# ISEPIC_Cartridge_for_C64.net
KiCad netlist of a schematic drawn in Altium Designer
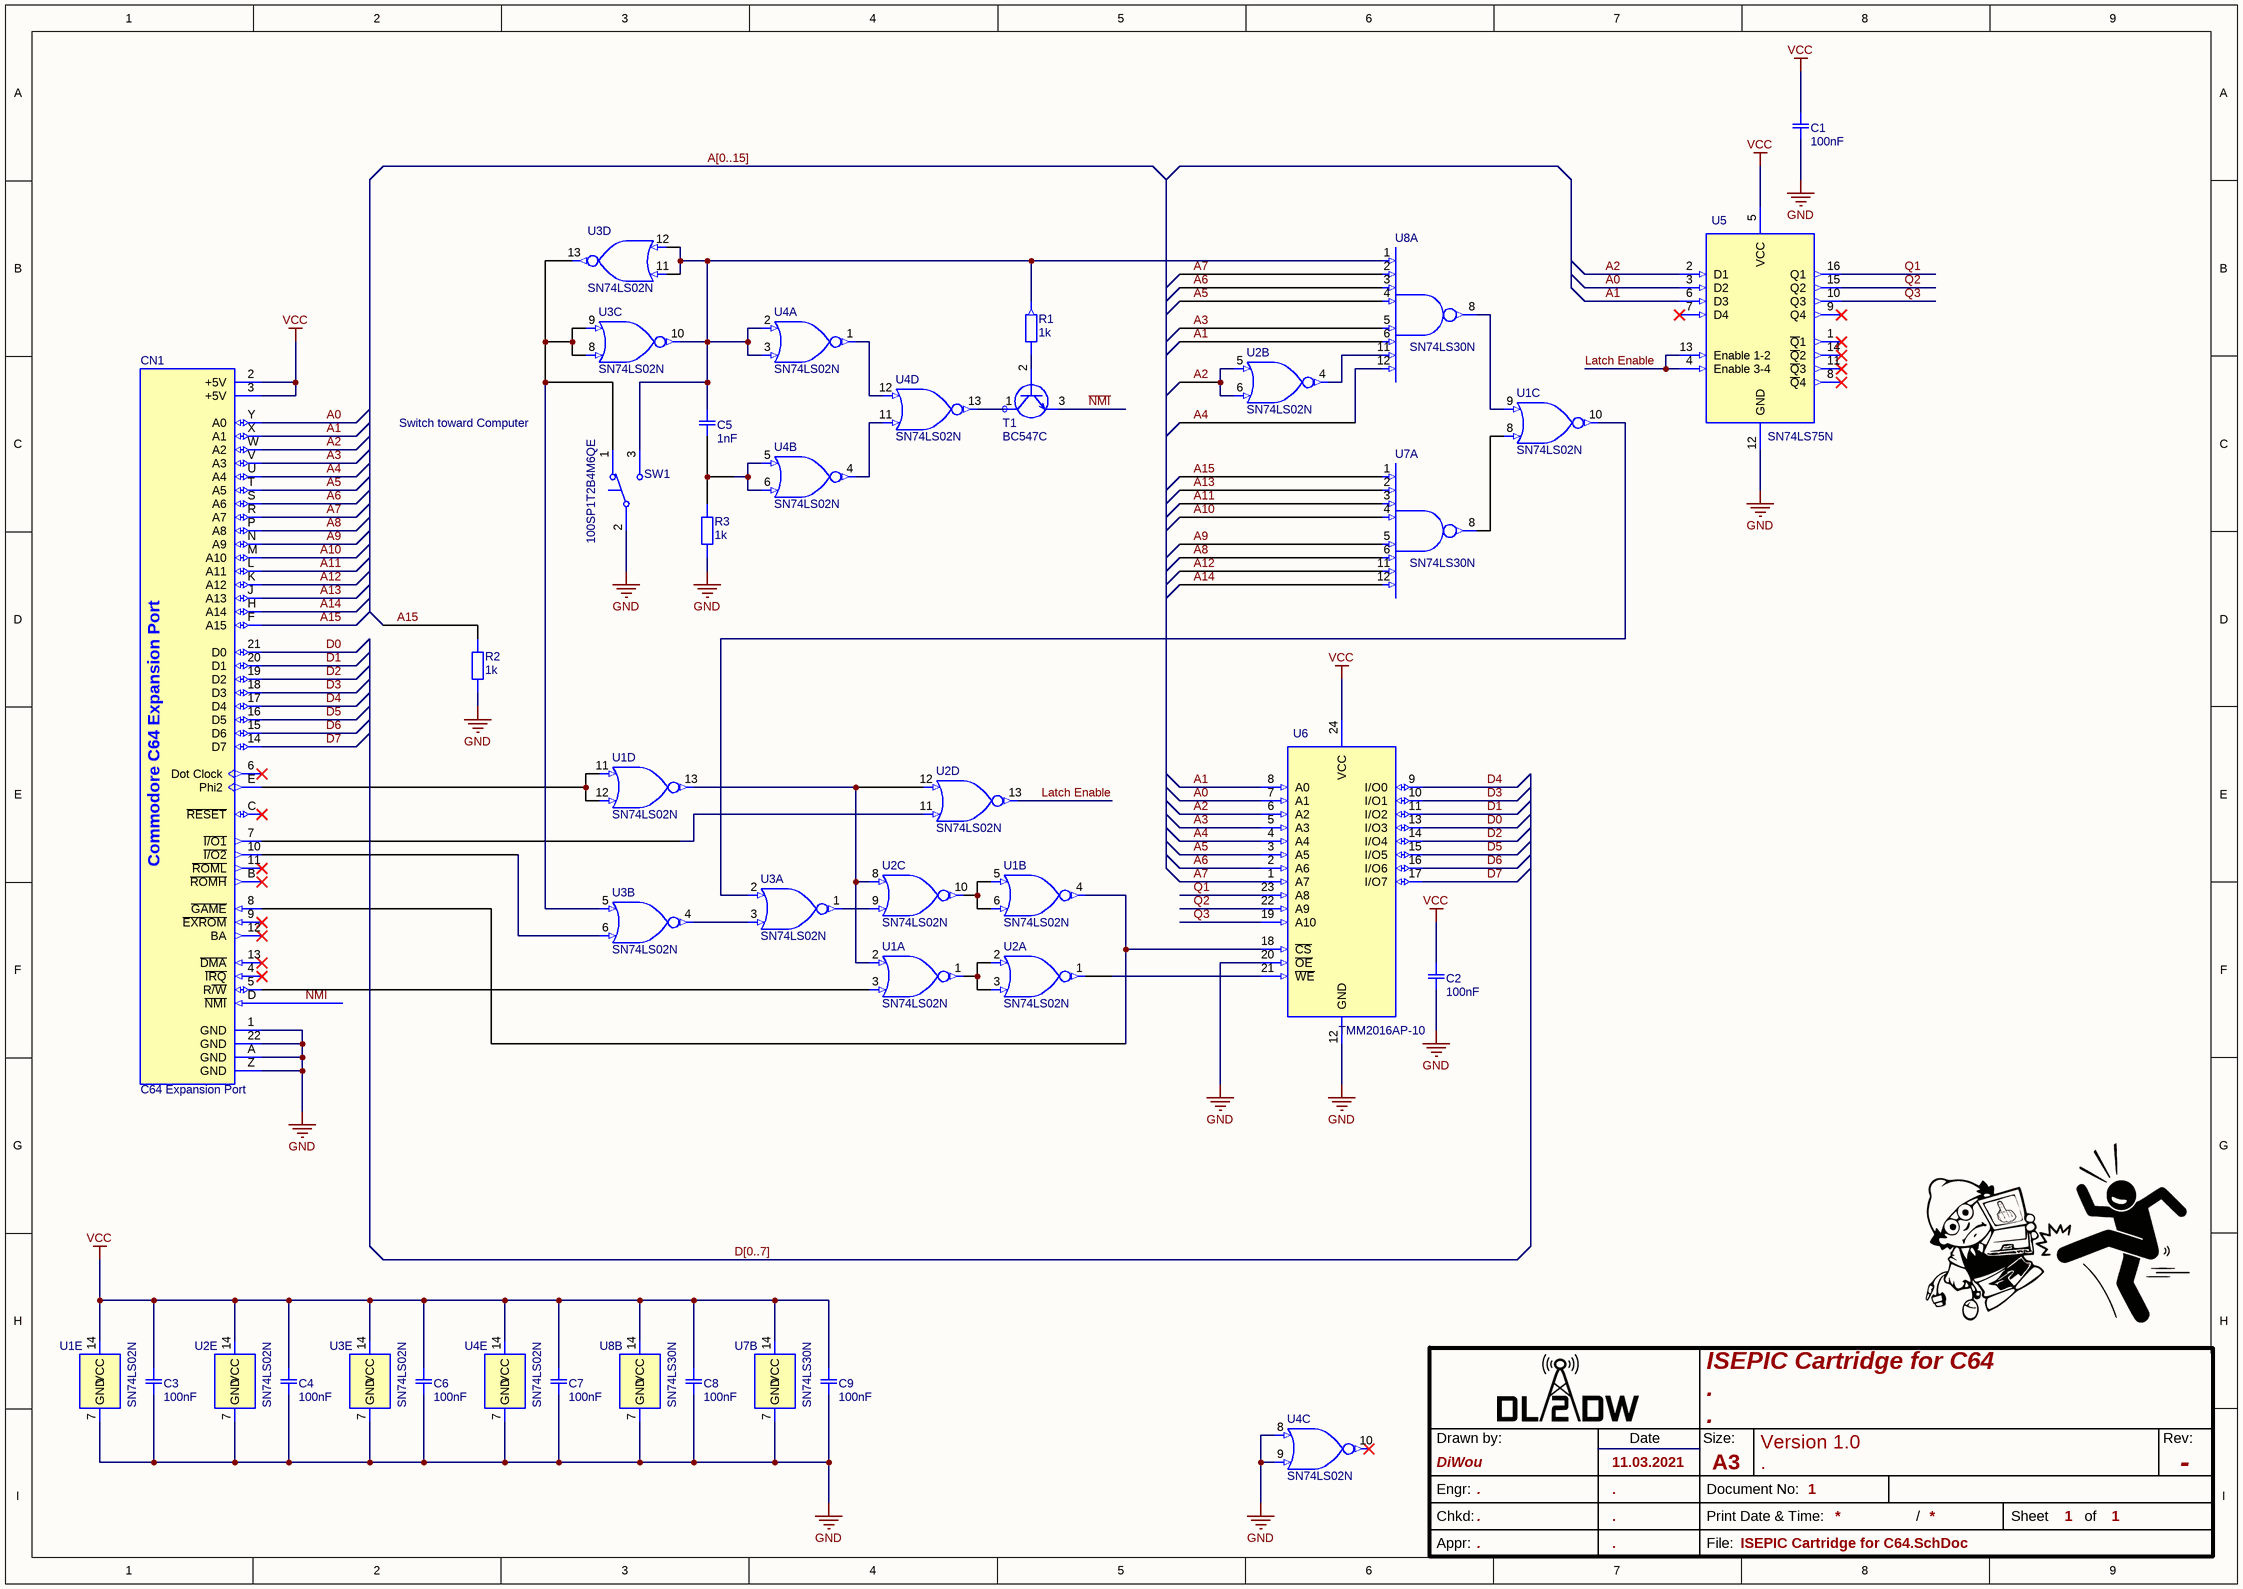
[diagram p0: ISEPIC Cartridge for C64.SchDoc]

(export (version "E")
  (design (tool "Eeschema 10.0.6"))
  (components
    (comp (ref "C1")
      (value "100nF")
      (footprint "CAP Disc 100nF P2.54mm D5.5mm T3mm")
      (description "Ceramic Disc Capacitors 100nF -20%~+80% 50V Through Hole,P=2.54mm RoHS")
      (libsource (lib "PCB-Tech Cloud") (part "Capacitor"))
    )
    (comp (ref "C2")
      (value "100nF")
      (footprint "CAP Disc 100nF P2.54mm D5.5mm T3mm")
      (description "Ceramic Disc Capacitors 100nF -20%~+80% 50V Through Hole,P=2.54mm RoHS")
      (libsource (lib "PCB-Tech Cloud") (part "Capacitor"))
    )
    (comp (ref "C3")
      (value "100nF")
      (footprint "CAP Disc 100nF P2.54mm D5.5mm T3mm")
      (description "Ceramic Disc Capacitors 100nF -20%~+80% 50V Through Hole,P=2.54mm RoHS")
      (libsource (lib "PCB-Tech Cloud") (part "Capacitor"))
    )
    (comp (ref "C4")
      (value "100nF")
      (footprint "CAP Disc 100nF P2.54mm D5.5mm T3mm")
      (description "Ceramic Disc Capacitors 100nF -20%~+80% 50V Through Hole,P=2.54mm RoHS")
      (libsource (lib "PCB-Tech Cloud") (part "Capacitor"))
    )
    (comp (ref "C5")
      (value "1nF")
      (footprint "K102J15C0GF5TL2")
      (description "CAP CER 1000PF 50V C0G/NP0 RAD")
      (fields (field (name "TOLERANCE") "5%") (field (name "VOLTAGE") "50V"))
      (libsource (lib "PCB-Tech Cloud") (part "Capacitor"))
    )
    (comp (ref "C6")
      (value "100nF")
      (footprint "CAP Disc 100nF P2.54mm D5.5mm T3mm")
      (description "Ceramic Disc Capacitors 100nF -20%~+80% 50V Through Hole,P=2.54mm RoHS")
      (libsource (lib "PCB-Tech Cloud") (part "Capacitor"))
    )
    (comp (ref "C7")
      (value "100nF")
      (footprint "CAP Disc 100nF P2.54mm D5.5mm T3mm")
      (description "Ceramic Disc Capacitors 100nF -20%~+80% 50V Through Hole,P=2.54mm RoHS")
      (libsource (lib "PCB-Tech Cloud") (part "Capacitor"))
    )
    (comp (ref "C8")
      (value "100nF")
      (footprint "CAP Disc 100nF P2.54mm D5.5mm T3mm")
      (description "Ceramic Disc Capacitors 100nF -20%~+80% 50V Through Hole,P=2.54mm RoHS")
      (libsource (lib "PCB-Tech Cloud") (part "Capacitor"))
    )
    (comp (ref "C9")
      (value "100nF")
      (footprint "CAP Disc 100nF P2.54mm D5.5mm T3mm")
      (description "Ceramic Disc Capacitors 100nF -20%~+80% 50V Through Hole,P=2.54mm RoHS")
      (libsource (lib "PCB-Tech Cloud") (part "Capacitor"))
    )
    (comp (ref "CN1")
      (value "C64 Expansion Port")
      (footprint "C64 Expansion Port EDGE Connector")
      (description "Expansion Port EDGE Connector for Interface Cards")
      (libsource (lib "PCB-Tech Cloud") (part "C64 Expansion Port"))
    )
    (comp (ref "R1")
      (value "1k")
      (footprint "1,0 kOhm R Axial DIN0207 L6.3mm D2.5mm P7.62mm Horizontal")
      (description "RES 1K OHM 1/4W 5% AXIAL")
      (fields (field (name "TOLERANCE") "5%"))
      (libsource (lib "PCB-Tech Cloud") (part "Resistor"))
    )
    (comp (ref "R2")
      (value "1k")
      (footprint "1,0 kOhm R Axial DIN0207 L6.3mm D2.5mm P7.62mm Horizontal")
      (description "RES 1K OHM 1/4W 5% AXIAL")
      (fields (field (name "TOLERANCE") "5%"))
      (libsource (lib "PCB-Tech Cloud") (part "Resistor"))
    )
    (comp (ref "R3")
      (value "1k")
      (footprint "1,0 kOhm R Axial DIN0207 L6.3mm D2.5mm P7.62mm Horizontal")
      (description "RES 1K OHM 1/4W 5% AXIAL")
      (fields (field (name "TOLERANCE") "5%"))
      (libsource (lib "PCB-Tech Cloud") (part "Resistor"))
    )
    (comp (ref "SW1")
      (value "100SP1T2B4M6QE")
      (footprint "Toogle Switch SPDT 100SP1T2B4M6QE")
      (description "SWITCH TOGGLE SPDT 5A 120V")
      (libsource (lib "PCB-Tech Cloud") (part "Switch Push SPDT"))
    )
    (comp (ref "T1")
      (value "BC547C")
      (footprint "BC547C")
      (description "BC547C Diotec Bipolar NPN Transistor 45V")
      (libsource (lib "PCB-Tech Cloud") (part "Transistor NPN CBE"))
    )
    (comp (ref "U1")
      (value "SN74LS02N")
      (footprint "SN74LS02N with Socket")
      (description "IC GATE NOR 4CH 2-INP 14DIP")
      (libsource (lib "PCB-Tech Cloud") (part "74xx02"))
    )
    (comp (ref "U2")
      (value "SN74LS02N")
      (footprint "SN74LS02N with Socket")
      (description "IC GATE NOR 4CH 2-INP 14DIP")
      (libsource (lib "") (part "74xx02_1"))
    )
    (comp (ref "U3")
      (value "SN74LS02N")
      (footprint "SN74LS02N with Socket")
      (description "IC GATE NOR 4CH 2-INP 14DIP")
      (libsource (lib "PCB-Tech Cloud") (part "74xx02"))
    )
    (comp (ref "U4")
      (value "SN74LS02N")
      (footprint "SN74LS02N with Socket")
      (description "IC GATE NOR 4CH 2-INP 14DIP")
      (libsource (lib "PCB-Tech Cloud") (part "74xx02"))
    )
    (comp (ref "U5")
      (value "SN74LS75N")
      (footprint "SN74LS75N with Socket")
      (description "Latch Transparent 4-CH D-Type 16-Pin PDIP Tube")
      (libsource (lib "PCB-Tech Cloud") (part "74xx75"))
    )
    (comp (ref "U6")
      (value "TMM2016AP-10")
      (footprint "Toshiba TMM2016AP-10 - with Socket")
      (description "Integrated Circuit Memory 2016/TMM2016AP10 TOSHIBA Static RAM memory prog. volatille KX8=2")
      (libsource (lib "PCB-Tech Cloud") (part "2048 WORD x 8 BIT STATIC RAM"))
    )
    (comp (ref "U7")
      (value "SN74LS30N")
      (footprint "SN74LS30N with Socket")
      (description "IC GATE NAND 1CH 8-INP 14DIP")
      (libsource (lib "PCB-Tech Cloud") (part "74xx30"))
    )
    (comp (ref "U8")
      (value "SN74LS30N")
      (footprint "SN74LS30N with Socket")
      (description "IC GATE NAND 1CH 8-INP 14DIP")
      (libsource (lib "PCB-Tech Cloud") (part "74xx30"))
    )
  )
  (nets
    (net (code "1") (name "/A0") (class "Default")
      (node (ref "CN1") (pin "Y") (pinfunction "A0_Y") (pintype "bidirectional"))
      (node (ref "U5") (pin "3") (pinfunction "D2_3") (pintype "input"))
      (node (ref "U6") (pin "7") (pinfunction "A1_7") (pintype "input"))
    )
    (net (code "2") (name "/A1") (class "Default")
      (node (ref "CN1") (pin "X") (pinfunction "A1_X") (pintype "bidirectional"))
      (node (ref "U5") (pin "6") (pinfunction "D3_6") (pintype "input"))
      (node (ref "U6") (pin "8") (pinfunction "A0_8") (pintype "input"))
      (node (ref "U8") (pin "6") (pinfunction "F_6") (pintype "input"))
    )
    (net (code "3") (name "/A2") (class "Default")
      (node (ref "CN1") (pin "W") (pinfunction "A2_W") (pintype "bidirectional"))
      (node (ref "U2") (pin "5") (pinfunction "2A_5") (pintype "input"))
      (node (ref "U2") (pin "6") (pinfunction "2B_6") (pintype "input"))
      (node (ref "U5") (pin "2") (pinfunction "D1_2") (pintype "input"))
      (node (ref "U6") (pin "6") (pinfunction "A2_6") (pintype "input"))
    )
    (net (code "4") (name "/A3") (class "Default")
      (node (ref "CN1") (pin "V") (pinfunction "A3_V") (pintype "bidirectional"))
      (node (ref "U6") (pin "5") (pinfunction "A3_5") (pintype "input"))
      (node (ref "U8") (pin "5") (pinfunction "E_5") (pintype "input"))
    )
    (net (code "5") (name "/A4") (class "Default")
      (node (ref "CN1") (pin "U") (pinfunction "A4_U") (pintype "bidirectional"))
      (node (ref "U6") (pin "4") (pinfunction "A4_4") (pintype "input"))
      (node (ref "U8") (pin "12") (pinfunction "H_12") (pintype "input"))
    )
    (net (code "6") (name "/A5") (class "Default")
      (node (ref "CN1") (pin "T") (pinfunction "A5_T") (pintype "bidirectional"))
      (node (ref "U6") (pin "3") (pinfunction "A5_3") (pintype "input"))
      (node (ref "U8") (pin "4") (pinfunction "D_4") (pintype "input"))
    )
    (net (code "7") (name "/A6") (class "Default")
      (node (ref "CN1") (pin "S") (pinfunction "A6_S") (pintype "bidirectional"))
      (node (ref "U6") (pin "2") (pinfunction "A6_2") (pintype "input"))
      (node (ref "U8") (pin "3") (pinfunction "C_3") (pintype "input"))
    )
    (net (code "8") (name "/A7") (class "Default")
      (node (ref "CN1") (pin "R") (pinfunction "A7_R") (pintype "bidirectional"))
      (node (ref "U6") (pin "1") (pinfunction "A7_1") (pintype "input"))
      (node (ref "U8") (pin "2") (pinfunction "B_2") (pintype "input"))
    )
    (net (code "9") (name "/A8") (class "Default")
      (node (ref "CN1") (pin "P") (pinfunction "A8_P") (pintype "bidirectional"))
      (node (ref "U7") (pin "6") (pinfunction "F_6") (pintype "input"))
    )
    (net (code "10") (name "/A9") (class "Default")
      (node (ref "CN1") (pin "N") (pinfunction "A9_N") (pintype "bidirectional"))
      (node (ref "U7") (pin "5") (pinfunction "E_5") (pintype "input"))
    )
    (net (code "11") (name "/A10") (class "Default")
      (node (ref "CN1") (pin "M") (pinfunction "A10_M") (pintype "bidirectional"))
      (node (ref "U7") (pin "4") (pinfunction "D_4") (pintype "input"))
    )
    (net (code "12") (name "/A11") (class "Default")
      (node (ref "CN1") (pin "L") (pinfunction "A11_L") (pintype "bidirectional"))
      (node (ref "U7") (pin "3") (pinfunction "C_3") (pintype "input"))
    )
    (net (code "13") (name "/A12") (class "Default")
      (node (ref "CN1") (pin "K") (pinfunction "A12_K") (pintype "bidirectional"))
      (node (ref "U7") (pin "11") (pinfunction "F_11") (pintype "input"))
    )
    (net (code "14") (name "/A13") (class "Default")
      (node (ref "CN1") (pin "J") (pinfunction "A13_J") (pintype "bidirectional"))
      (node (ref "U7") (pin "2") (pinfunction "B_2") (pintype "input"))
    )
    (net (code "15") (name "/A14") (class "Default")
      (node (ref "CN1") (pin "H") (pinfunction "A14_H") (pintype "bidirectional"))
      (node (ref "U7") (pin "12") (pinfunction "H_12") (pintype "input"))
    )
    (net (code "16") (name "/A15") (class "Default")
      (node (ref "CN1") (pin "F") (pinfunction "A15_F") (pintype "bidirectional"))
      (node (ref "R2") (pin "1") (pinfunction "1_1") (pintype "passive"))
      (node (ref "U7") (pin "1") (pinfunction "A_1") (pintype "input"))
    )
    (net (code "18") (name "/D0") (class "Default")
      (node (ref "CN1") (pin "21") (pinfunction "D0_21") (pintype "bidirectional"))
      (node (ref "U6") (pin "13") (pinfunction "I/O3_13") (pintype "bidirectional"))
    )
    (net (code "19") (name "/D1") (class "Default")
      (node (ref "CN1") (pin "20") (pinfunction "D1_20") (pintype "bidirectional"))
      (node (ref "U6") (pin "11") (pinfunction "I/O2_11") (pintype "bidirectional"))
    )
    (net (code "20") (name "/D2") (class "Default")
      (node (ref "CN1") (pin "19") (pinfunction "D2_19") (pintype "bidirectional"))
      (node (ref "U6") (pin "14") (pinfunction "I/O4_14") (pintype "bidirectional"))
    )
    (net (code "21") (name "/D3") (class "Default")
      (node (ref "CN1") (pin "18") (pinfunction "D3_18") (pintype "bidirectional"))
      (node (ref "U6") (pin "10") (pinfunction "I/O1_10") (pintype "bidirectional"))
    )
    (net (code "22") (name "/D4") (class "Default")
      (node (ref "CN1") (pin "17") (pinfunction "D4_17") (pintype "bidirectional"))
      (node (ref "U6") (pin "9") (pinfunction "I/O0_9") (pintype "bidirectional"))
    )
    (net (code "23") (name "/D5") (class "Default")
      (node (ref "CN1") (pin "16") (pinfunction "D5_16") (pintype "bidirectional"))
      (node (ref "U6") (pin "15") (pinfunction "I/O5_15") (pintype "bidirectional"))
    )
    (net (code "24") (name "/D6") (class "Default")
      (node (ref "CN1") (pin "15") (pinfunction "D6_15") (pintype "bidirectional"))
      (node (ref "U6") (pin "16") (pinfunction "I/O6_16") (pintype "bidirectional"))
    )
    (net (code "25") (name "/D7") (class "Default")
      (node (ref "CN1") (pin "14") (pinfunction "D7_14") (pintype "bidirectional"))
      (node (ref "U6") (pin "17") (pinfunction "I/O7_17") (pintype "bidirectional"))
    )
    (net (code "27") (name "/Latch Enable") (class "Default")
      (node (ref "U2") (pin "13") (pinfunction "4Y_13") (pintype "output"))
      (node (ref "U5") (pin "13") (pinfunction "Enable_1-2_13") (pintype "input"))
      (node (ref "U5") (pin "4") (pinfunction "Enable_3-4_4") (pintype "input"))
    )
    (net (code "28") (name "/Q1") (class "Default")
      (node (ref "U5") (pin "16") (pinfunction "Q1_16") (pintype "output"))
      (node (ref "U6") (pin "23") (pinfunction "A8_23") (pintype "input"))
    )
    (net (code "29") (name "/Q2") (class "Default")
      (node (ref "U5") (pin "15") (pinfunction "Q2_15") (pintype "output"))
      (node (ref "U6") (pin "22") (pinfunction "A9_22") (pintype "input"))
    )
    (net (code "30") (name "/Q3") (class "Default")
      (node (ref "U5") (pin "10") (pinfunction "Q3_10") (pintype "output"))
      (node (ref "U6") (pin "19") (pinfunction "A10_19") (pintype "input"))
    )
    (net (code "31") (name "/~{NMI}") (class "Default")
      (node (ref "CN1") (pin "D") (pinfunction "~{NMI}_D") (pintype "input"))
      (node (ref "T1") (pin "3") (pinfunction "3_3") (pintype "passive"))
    )
    (net (code "32") (name "GND") (class "Default")
      (node (ref "C1") (pin "1") (pinfunction "1_1") (pintype "passive"))
      (node (ref "C2") (pin "1") (pinfunction "1_1") (pintype "passive"))
      (node (ref "C3") (pin "1") (pinfunction "1_1") (pintype "passive"))
      (node (ref "C4") (pin "1") (pinfunction "1_1") (pintype "passive"))
      (node (ref "C6") (pin "1") (pinfunction "1_1") (pintype "passive"))
      (node (ref "C7") (pin "1") (pinfunction "1_1") (pintype "passive"))
      (node (ref "C8") (pin "1") (pinfunction "1_1") (pintype "passive"))
      (node (ref "C9") (pin "1") (pinfunction "1_1") (pintype "passive"))
      (node (ref "CN1") (pin "1") (pinfunction "GND_1") (pintype "power_in"))
      (node (ref "CN1") (pin "22") (pinfunction "GND_22") (pintype "power_in"))
      (node (ref "CN1") (pin "A") (pinfunction "GND_A") (pintype "power_in"))
      (node (ref "CN1") (pin "Z") (pinfunction "GND_Z") (pintype "power_in"))
      (node (ref "R2") (pin "2") (pinfunction "2_2") (pintype "passive"))
      (node (ref "R3") (pin "1") (pinfunction "1_1") (pintype "passive"))
      (node (ref "SW1") (pin "2") (pinfunction "2_2") (pintype "passive"))
      (node (ref "U1") (pin "7") (pinfunction "GND_7") (pintype "passive"))
      (node (ref "U2") (pin "7") (pinfunction "GND_7") (pintype "passive"))
      (node (ref "U3") (pin "7") (pinfunction "GND_7") (pintype "passive"))
      (node (ref "U4") (pin "7") (pinfunction "GND_7") (pintype "passive"))
      (node (ref "U4") (pin "8") (pinfunction "3A_8") (pintype "input"))
      (node (ref "U4") (pin "9") (pinfunction "3B_9") (pintype "input"))
      (node (ref "U5") (pin "12") (pinfunction "GND_12") (pintype "power_in"))
      (node (ref "U6") (pin "12") (pinfunction "GND_12") (pintype "passive"))
      (node (ref "U6") (pin "20") (pinfunction "~{OE}_20") (pintype "input"))
      (node (ref "U7") (pin "7") (pinfunction "GND_7") (pintype "passive"))
      (node (ref "U8") (pin "7") (pinfunction "GND_7") (pintype "passive"))
    )
    (net (code "33") (name "Net-(CN1-Phi2)") (class "Default")
      (node (ref "CN1") (pin "E") (pinfunction "Phi2_E") (pintype "output"))
      (node (ref "U1") (pin "11") (pinfunction "4A_11") (pintype "input"))
      (node (ref "U1") (pin "12") (pinfunction "4B_12") (pintype "input"))
    )
    (net (code "34") (name "Net-(CN1-R~{{slash}W})") (class "Default")
      (node (ref "CN1") (pin "5") (pinfunction "R~{/W}_5") (pintype "bidirectional"))
      (node (ref "U1") (pin "3") (pinfunction "1B_3") (pintype "input"))
    )
    (net (code "35") (name "Net-(CN1-~{GAME})") (class "Default")
      (node (ref "CN1") (pin "8") (pinfunction "~{GAME}_8") (pintype "input"))
      (node (ref "U1") (pin "4") (pinfunction "2Y_4") (pintype "output"))
      (node (ref "U6") (pin "18") (pinfunction "~{CS}_18") (pintype "input"))
    )
    (net (code "36") (name "Net-(CN1-~{I{slash}O1})") (class "Default")
      (node (ref "CN1") (pin "7") (pinfunction "~{I/O1}_7") (pintype "output"))
      (node (ref "U2") (pin "11") (pinfunction "4A_11") (pintype "input"))
    )
    (net (code "37") (name "Net-(CN1-~{I{slash}O2})") (class "Default")
      (node (ref "CN1") (pin "10") (pinfunction "~{I/O2}_10") (pintype "output"))
      (node (ref "U3") (pin "6") (pinfunction "2B_6") (pintype "input"))
    )
    (net (code "38") (name "Net-(R1-Pad1)") (class "Default")
      (node (ref "R1") (pin "1") (pinfunction "1_1") (pintype "passive"))
      (node (ref "T1") (pin "2") (pinfunction "2_2") (pintype "passive"))
    )
    (net (code "39") (name "Net-(U1A-1A)") (class "Default")
      (node (ref "U1") (pin "13") (pinfunction "4Y_13") (pintype "output"))
      (node (ref "U1") (pin "2") (pinfunction "1A_2") (pintype "input"))
      (node (ref "U2") (pin "12") (pinfunction "4B_12") (pintype "input"))
      (node (ref "U2") (pin "8") (pinfunction "3A_8") (pintype "input"))
    )
    (net (code "40") (name "Net-(U1A-1Y)") (class "Default")
      (node (ref "U1") (pin "1") (pinfunction "1Y_1") (pintype "output"))
      (node (ref "U2") (pin "2") (pinfunction "1A_2") (pintype "input"))
      (node (ref "U2") (pin "3") (pinfunction "1B_3") (pintype "input"))
    )
    (net (code "41") (name "Net-(U1B-2A)") (class "Default")
      (node (ref "U1") (pin "5") (pinfunction "2A_5") (pintype "input"))
      (node (ref "U1") (pin "6") (pinfunction "2B_6") (pintype "input"))
      (node (ref "U2") (pin "10") (pinfunction "3Y_10") (pintype "output"))
    )
    (net (code "42") (name "Net-(U1C-3A)") (class "Default")
      (node (ref "U1") (pin "8") (pinfunction "3A_8") (pintype "input"))
      (node (ref "U7") (pin "8") (pinfunction "1Y_8") (pintype "output"))
    )
    (net (code "43") (name "Net-(U1C-3B)") (class "Default")
      (node (ref "U1") (pin "9") (pinfunction "3B_9") (pintype "input"))
      (node (ref "U8") (pin "8") (pinfunction "1Y_8") (pintype "output"))
    )
    (net (code "44") (name "Net-(U1C-3Y)") (class "Default")
      (node (ref "U1") (pin "10") (pinfunction "3Y_10") (pintype "output"))
      (node (ref "U3") (pin "2") (pinfunction "1A_2") (pintype "input"))
    )
    (net (code "45") (name "Net-(U2A-1Y)") (class "Default")
      (node (ref "U2") (pin "1") (pinfunction "1Y_1") (pintype "output"))
      (node (ref "U6") (pin "21") (pinfunction "~{WE}_21") (pintype "input"))
    )
    (net (code "46") (name "Net-(U2B-2Y)") (class "Default")
      (node (ref "U2") (pin "4") (pinfunction "2Y_4") (pintype "output"))
      (node (ref "U8") (pin "11") (pinfunction "F_11") (pintype "input"))
    )
    (net (code "47") (name "Net-(U2C-3B)") (class "Default")
      (node (ref "U2") (pin "9") (pinfunction "3B_9") (pintype "input"))
      (node (ref "U3") (pin "1") (pinfunction "1Y_1") (pintype "output"))
    )
    (net (code "48") (name "Net-(U3A-1B)") (class "Default")
      (node (ref "U3") (pin "3") (pinfunction "1B_3") (pintype "input"))
      (node (ref "U3") (pin "4") (pinfunction "2Y_4") (pintype "output"))
    )
    (net (code "49") (name "Net-(U3B-2A)") (class "Default")
      (node (ref "SW1") (pin "1") (pinfunction "1_1") (pintype "passive"))
      (node (ref "U3") (pin "13") (pinfunction "4Y_13") (pintype "output"))
      (node (ref "U3") (pin "5") (pinfunction "2A_5") (pintype "input"))
      (node (ref "U3") (pin "8") (pinfunction "3A_8") (pintype "input"))
      (node (ref "U3") (pin "9") (pinfunction "3B_9") (pintype "input"))
    )
    (net (code "50") (name "Net-(U3C-3Y)") (class "Default")
      (node (ref "C5") (pin "1") (pinfunction "1_1") (pintype "passive"))
      (node (ref "R1") (pin "2") (pinfunction "2_2") (pintype "passive"))
      (node (ref "SW1") (pin "3") (pinfunction "3_3") (pintype "passive"))
      (node (ref "U3") (pin "10") (pinfunction "3Y_10") (pintype "output"))
      (node (ref "U3") (pin "11") (pinfunction "4A_11") (pintype "input"))
      (node (ref "U3") (pin "12") (pinfunction "4B_12") (pintype "input"))
      (node (ref "U4") (pin "2") (pinfunction "1A_2") (pintype "input"))
      (node (ref "U4") (pin "3") (pinfunction "1B_3") (pintype "input"))
      (node (ref "U8") (pin "1") (pinfunction "A_1") (pintype "input"))
    )
    (net (code "51") (name "Net-(U4A-1Y)") (class "Default")
      (node (ref "U4") (pin "1") (pinfunction "1Y_1") (pintype "output"))
      (node (ref "U4") (pin "12") (pinfunction "4B_12") (pintype "input"))
    )
    (net (code "52") (name "Net-(U4B-2A)") (class "Default")
      (node (ref "C5") (pin "2") (pinfunction "2_2") (pintype "passive"))
      (node (ref "R3") (pin "2") (pinfunction "2_2") (pintype "passive"))
      (node (ref "U4") (pin "5") (pinfunction "2A_5") (pintype "input"))
      (node (ref "U4") (pin "6") (pinfunction "2B_6") (pintype "input"))
    )
    (net (code "53") (name "Net-(U4B-2Y)") (class "Default")
      (node (ref "U4") (pin "11") (pinfunction "4A_11") (pintype "input"))
      (node (ref "U4") (pin "4") (pinfunction "2Y_4") (pintype "output"))
    )
    (net (code "54") (name "Net-(U4D-4Y)") (class "Default")
      (node (ref "T1") (pin "1") (pinfunction "1_1") (pintype "passive"))
      (node (ref "U4") (pin "13") (pinfunction "4Y_13") (pintype "output"))
    )
    (net (code "55") (name "VCC") (class "Default")
      (node (ref "C1") (pin "2") (pinfunction "2_2") (pintype "passive"))
      (node (ref "C2") (pin "2") (pinfunction "2_2") (pintype "passive"))
      (node (ref "C3") (pin "2") (pinfunction "2_2") (pintype "passive"))
      (node (ref "C4") (pin "2") (pinfunction "2_2") (pintype "passive"))
      (node (ref "C6") (pin "2") (pinfunction "2_2") (pintype "passive"))
      (node (ref "C7") (pin "2") (pinfunction "2_2") (pintype "passive"))
      (node (ref "C8") (pin "2") (pinfunction "2_2") (pintype "passive"))
      (node (ref "C9") (pin "2") (pinfunction "2_2") (pintype "passive"))
      (node (ref "CN1") (pin "2") (pinfunction "+5V_2") (pintype "power_in"))
      (node (ref "CN1") (pin "3") (pinfunction "+5V_3") (pintype "power_in"))
      (node (ref "U1") (pin "14") (pinfunction "VCC_14") (pintype "power_in"))
      (node (ref "U2") (pin "14") (pinfunction "VCC_14") (pintype "power_in"))
      (node (ref "U3") (pin "14") (pinfunction "VCC_14") (pintype "power_in"))
      (node (ref "U4") (pin "14") (pinfunction "VCC_14") (pintype "power_in"))
      (node (ref "U5") (pin "5") (pinfunction "VCC_5") (pintype "power_in"))
      (node (ref "U6") (pin "24") (pinfunction "VCC_24") (pintype "power_in"))
      (node (ref "U7") (pin "14") (pinfunction "VCC_14") (pintype "power_in"))
      (node (ref "U8") (pin "14") (pinfunction "VCC_14") (pintype "power_in"))
    )
    (net (code "56") (name "unconnected-(CN1-BA-Pad12)") (class "Default")
      (node (ref "CN1") (pin "12") (pinfunction "BA_12") (pintype "output+no_connect"))
    )
    (net (code "57") (name "unconnected-(CN1-Dot_Clock-Pad6)") (class "Default")
      (node (ref "CN1") (pin "6") (pinfunction "Dot_Clock_6") (pintype "output+no_connect"))
    )
    (net (code "58") (name "unconnected-(CN1-~{DMA}-Pad13)") (class "Default")
      (node (ref "CN1") (pin "13") (pinfunction "~{DMA}_13") (pintype "input+no_connect"))
    )
    (net (code "59") (name "unconnected-(CN1-~{EXROM}-Pad9)") (class "Default")
      (node (ref "CN1") (pin "9") (pinfunction "~{EXROM}_9") (pintype "input+no_connect"))
    )
    (net (code "60") (name "unconnected-(CN1-~{IRQ}-Pad4)") (class "Default")
      (node (ref "CN1") (pin "4") (pinfunction "~{IRQ}_4") (pintype "input+no_connect"))
    )
    (net (code "61") (name "unconnected-(CN1-~{RESET}-PadC)") (class "Default")
      (node (ref "CN1") (pin "C") (pinfunction "~{RESET}_C") (pintype "bidirectional+no_connect"))
    )
    (net (code "62") (name "unconnected-(CN1-~{ROMH}-PadB)") (class "Default")
      (node (ref "CN1") (pin "B") (pinfunction "~{ROMH}_B") (pintype "output+no_connect"))
    )
    (net (code "63") (name "unconnected-(CN1-~{ROML}-Pad11)") (class "Default")
      (node (ref "CN1") (pin "11") (pinfunction "~{ROML}_11") (pintype "output+no_connect"))
    )
    (net (code "64") (name "unconnected-(U4C-3Y-Pad10)") (class "Default")
      (node (ref "U4") (pin "10") (pinfunction "3Y_10") (pintype "output+no_connect"))
    )
    (net (code "65") (name "unconnected-(U5-D4-Pad7)") (class "Default")
      (node (ref "U5") (pin "7") (pinfunction "D4_7") (pintype "input+no_connect"))
    )
    (net (code "66") (name "unconnected-(U5-Q4-Pad9)") (class "Default")
      (node (ref "U5") (pin "9") (pinfunction "Q4_9") (pintype "output+no_connect"))
    )
    (net (code "67") (name "unconnected-(U5-~{Q}1-Pad1)") (class "Default")
      (node (ref "U5") (pin "1") (pinfunction "~{Q}1_1") (pintype "output+no_connect"))
    )
    (net (code "68") (name "unconnected-(U5-~{Q}2-Pad14)") (class "Default")
      (node (ref "U5") (pin "14") (pinfunction "~{Q}2_14") (pintype "output+no_connect"))
    )
    (net (code "69") (name "unconnected-(U5-~{Q}3-Pad11)") (class "Default")
      (node (ref "U5") (pin "11") (pinfunction "~{Q}3_11") (pintype "output+no_connect"))
    )
    (net (code "70") (name "unconnected-(U5-~{Q}4-Pad8)") (class "Default")
      (node (ref "U5") (pin "8") (pinfunction "~{Q}4_8") (pintype "output+no_connect"))
    )
    (net (code "71") (name "unconnected-(U7A-N{slash}C-Pad9)") (class "Default")
      (node (ref "U7") (pin "9") (pinfunction "N/C_9") (pintype "passive"))
    )
    (net (code "72") (name "unconnected-(U7A-N{slash}C-Pad10)") (class "Default")
      (node (ref "U7") (pin "10") (pinfunction "N/C_10") (pintype "passive"))
    )
    (net (code "73") (name "unconnected-(U7A-N{slash}C-Pad13)") (class "Default")
      (node (ref "U7") (pin "13") (pinfunction "N/C_13") (pintype "passive"))
    )
    (net (code "74") (name "unconnected-(U8A-N{slash}C-Pad9)") (class "Default")
      (node (ref "U8") (pin "9") (pinfunction "N/C_9") (pintype "passive"))
    )
    (net (code "75") (name "unconnected-(U8A-N{slash}C-Pad10)") (class "Default")
      (node (ref "U8") (pin "10") (pinfunction "N/C_10") (pintype "passive"))
    )
    (net (code "76") (name "unconnected-(U8A-N{slash}C-Pad13)") (class "Default")
      (node (ref "U8") (pin "13") (pinfunction "N/C_13") (pintype "passive"))
    )
  )
)
